# powerbutton.net
KiCad netlist of a schematic drawn in EAGLE
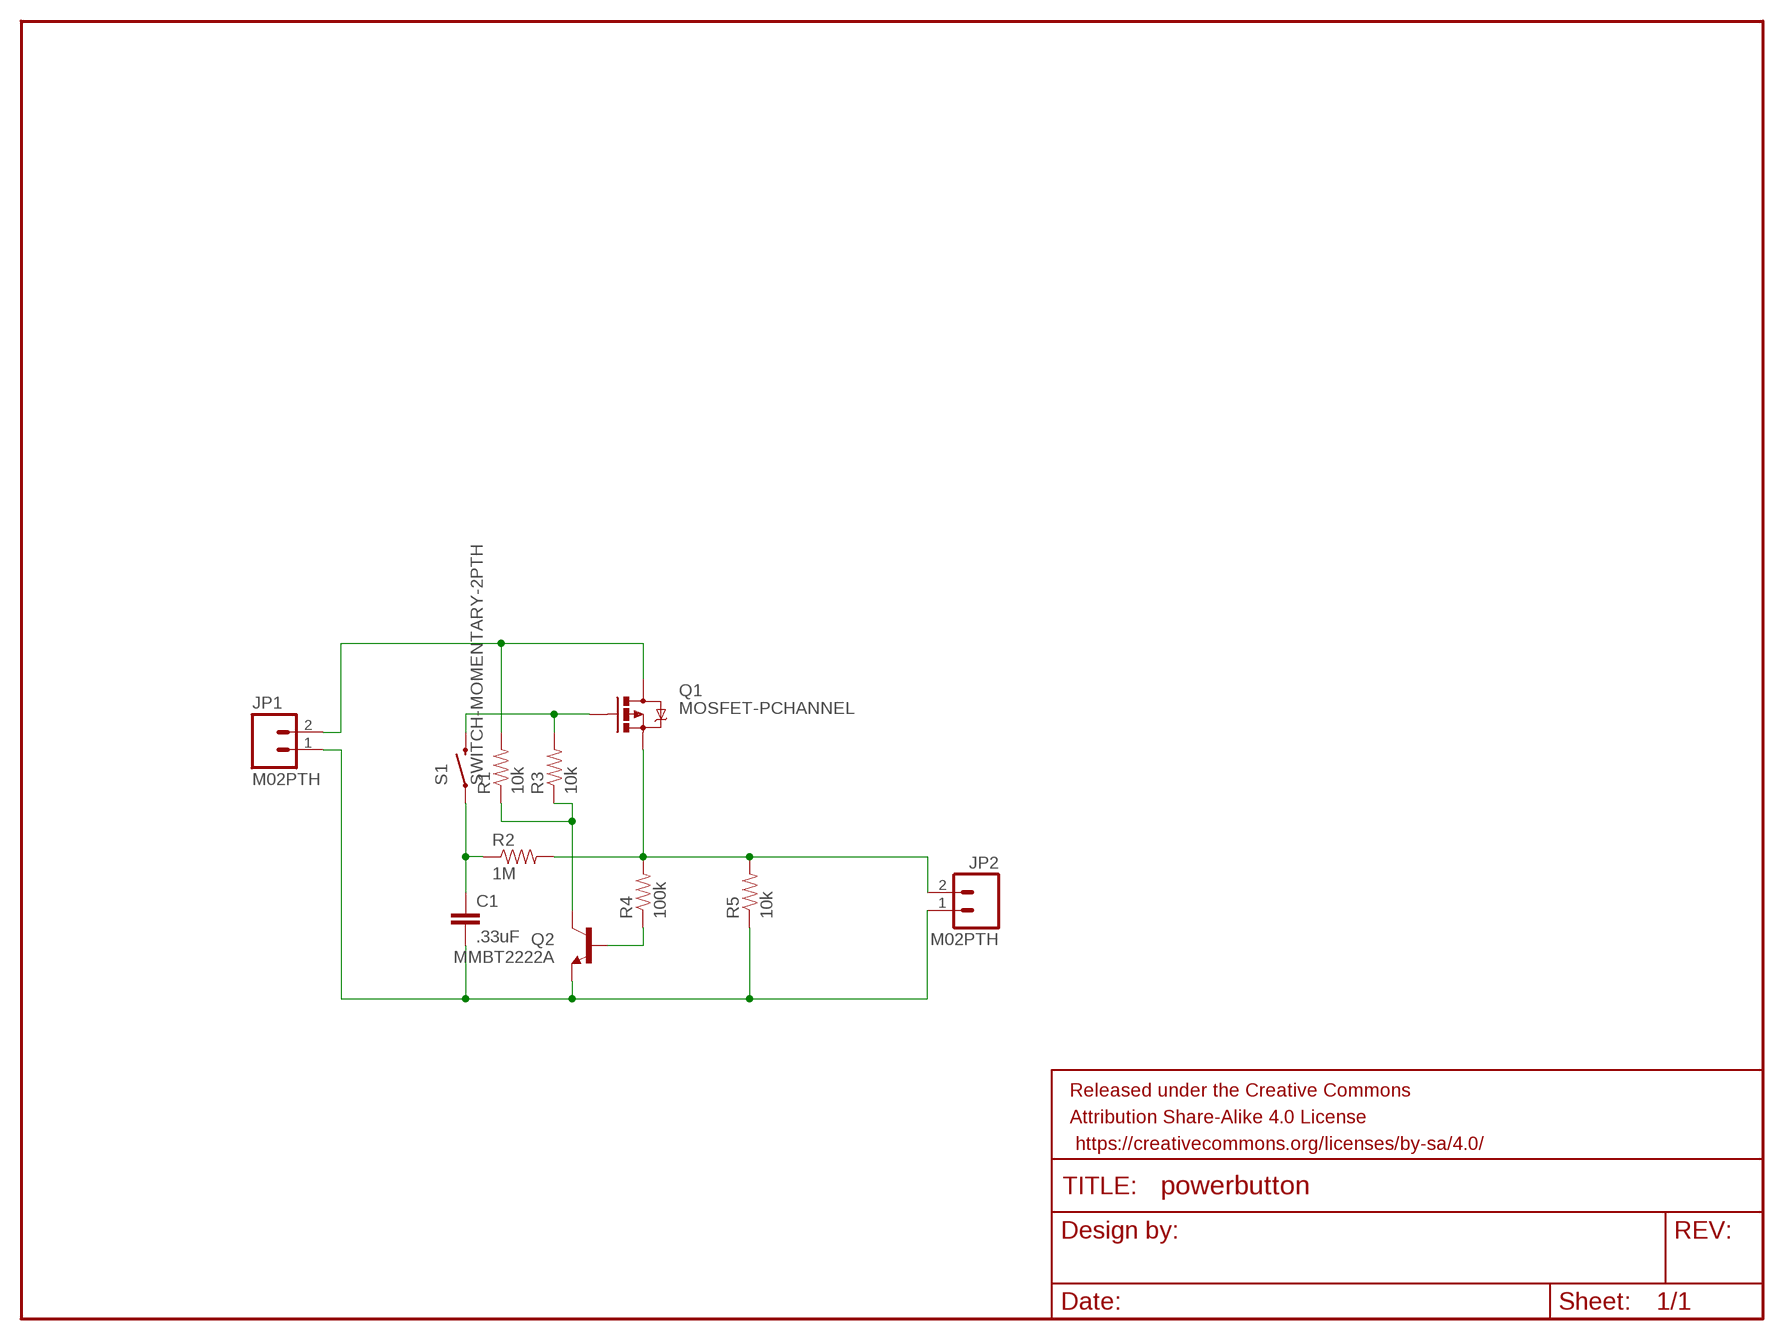
[diagram p0: schematic, sheet 1]

(export (version "E")
  (design (tool "Eeschema 10.0.6"))
  (components
    (comp (ref "C1")
      (value ".33uF")
      (footprint "eagle-import:0603-CAP")
      (libsource (lib "eagle-import") (part "CAP0603-CAP"))
    )
    (comp (ref "FRAME1")
      (value "FRAME-LETTER")
      (footprint "eagle-import:CREATIVE_COMMONS")
      (libsource (lib "eagle-import") (part "FRAME-LETTER"))
    )
    (comp (ref "JP1")
      (value "M02PTH")
      (footprint "eagle-import:1X02")
      (libsource (lib "eagle-import") (part "M02PTH"))
    )
    (comp (ref "JP2")
      (value "M02PTH")
      (footprint "eagle-import:1X02")
      (libsource (lib "eagle-import") (part "M02PTH"))
    )
    (comp (ref "Q1")
      (value "MOSFET-PCHANNEL")
      (footprint "eagle-import:SOT23-3")
      (libsource (lib "eagle-import") (part "MOSFET-PCHANNEL"))
    )
    (comp (ref "Q2")
      (value "MMBT2222A")
      (footprint "eagle-import:SOT23-3")
      (libsource (lib "eagle-import") (part "TRANSISTOR_NPNMMBT2222A"))
    )
    (comp (ref "R1")
      (value "10k")
      (footprint "eagle-import:0603-RES")
      (libsource (lib "eagle-import") (part "RESISTOR0603-RES"))
    )
    (comp (ref "R2")
      (value "1M")
      (footprint "eagle-import:0603-RES")
      (libsource (lib "eagle-import") (part "RESISTOR0603-RES"))
    )
    (comp (ref "R3")
      (value "10k")
      (footprint "eagle-import:0603-RES")
      (libsource (lib "eagle-import") (part "RESISTOR0603-RES"))
    )
    (comp (ref "R4")
      (value "100k")
      (footprint "eagle-import:0603-RES")
      (libsource (lib "eagle-import") (part "RESISTOR0603-RES"))
    )
    (comp (ref "R5")
      (value "10k")
      (footprint "eagle-import:0603-RES")
      (libsource (lib "eagle-import") (part "RESISTOR0603-RES"))
    )
    (comp (ref "S1")
      (value "SWITCH-MOMENTARY-2PTH")
      (footprint "eagle-import:TACTILE-PTH")
      (libsource (lib "eagle-import") (part "SWITCH-MOMENTARY-2PTH"))
    )
  )
  (nets
    (net (code "1") (name "Net-(C1-Pad1)") (class "Default")
      (node (ref "C1") (pin "1") (pinfunction "1_1") (pintype "passive"))
      (node (ref "R2") (pin "1") (pinfunction "1_1") (pintype "passive"))
      (node (ref "S1") (pin "1") (pinfunction "1_1") (pintype "passive"))
    )
    (net (code "2") (name "Net-(Q1-D)") (class "Default")
      (node (ref "JP1") (pin "2") (pinfunction "2_2") (pintype "passive"))
      (node (ref "Q1") (pin "3") (pinfunction "D_3") (pintype "passive"))
      (node (ref "R1") (pin "2") (pinfunction "2_2") (pintype "passive"))
    )
    (net (code "3") (name "Net-(Q1-G)") (class "Default")
      (node (ref "Q1") (pin "1") (pinfunction "G_1") (pintype "passive"))
      (node (ref "R3") (pin "2") (pinfunction "2_2") (pintype "passive"))
      (node (ref "S1") (pin "3") (pinfunction "2_3") (pintype "passive"))
    )
    (net (code "4") (name "Net-(Q1-S)") (class "Default")
      (node (ref "JP2") (pin "2") (pinfunction "2_2") (pintype "passive"))
      (node (ref "Q1") (pin "2") (pinfunction "S_2") (pintype "passive"))
      (node (ref "R2") (pin "2") (pinfunction "2_2") (pintype "passive"))
      (node (ref "R4") (pin "2") (pinfunction "2_2") (pintype "passive"))
      (node (ref "R5") (pin "2") (pinfunction "2_2") (pintype "passive"))
    )
    (net (code "5") (name "Net-(Q2-B)") (class "Default")
      (node (ref "Q2") (pin "1") (pinfunction "B_1") (pintype "passive"))
      (node (ref "R4") (pin "1") (pinfunction "1_1") (pintype "passive"))
    )
    (net (code "6") (name "Net-(Q2-C)") (class "Default")
      (node (ref "Q2") (pin "3") (pinfunction "C_3") (pintype "passive"))
      (node (ref "R1") (pin "1") (pinfunction "1_1") (pintype "passive"))
      (node (ref "R3") (pin "1") (pinfunction "1_1") (pintype "passive"))
    )
    (net (code "7") (name "Net-(Q2-E)") (class "Default")
      (node (ref "C1") (pin "2") (pinfunction "2_2") (pintype "passive"))
      (node (ref "JP1") (pin "1") (pinfunction "1_1") (pintype "passive"))
      (node (ref "JP2") (pin "1") (pinfunction "1_1") (pintype "passive"))
      (node (ref "Q2") (pin "2") (pinfunction "E_2") (pintype "passive"))
      (node (ref "R5") (pin "1") (pinfunction "1_1") (pintype "passive"))
    )
  )
)
